# 06_-_Voltage_Sense.net
KiCad netlist of a schematic drawn in Altium Designer
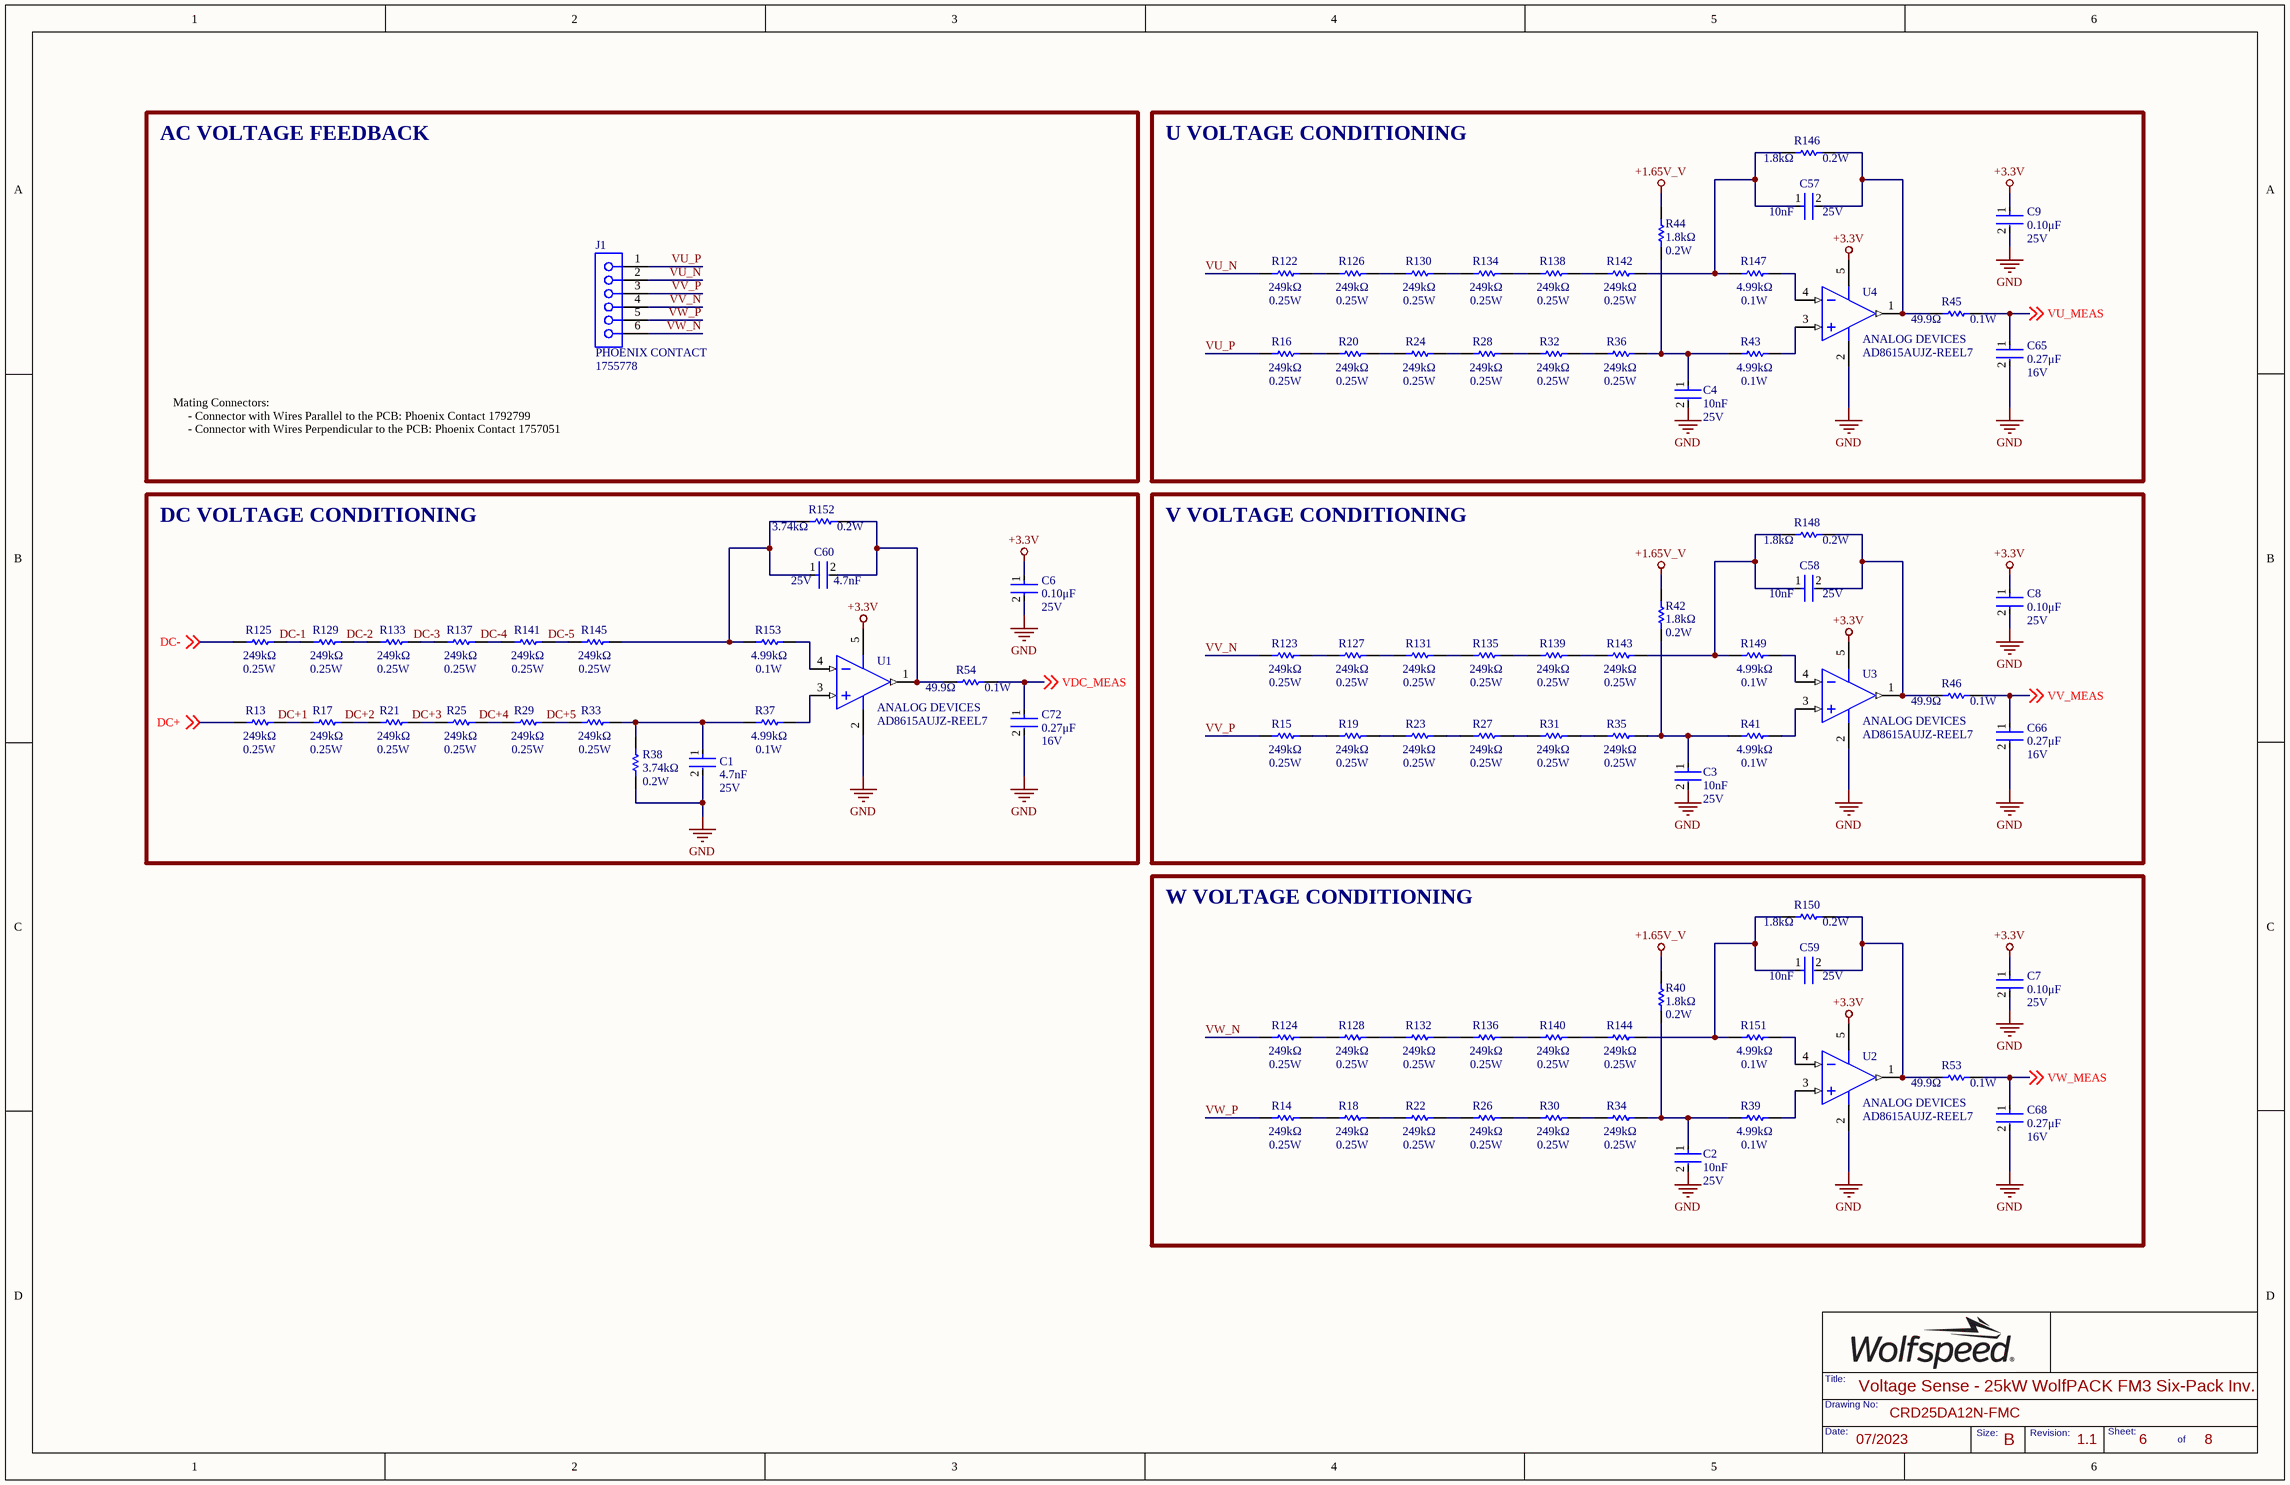
[diagram p0: 06 - Voltage Sense.SchDoc]

(export (version "E")
  (design (tool "Eeschema 10.0.6"))
  (components
    (comp (ref "C1")
      (value "C0603C472K3RAC7867")
      (footprint "FP-C0603C-CF-IPC_B")
      (description "CAP CER 4700PF 25V 10% X7R 0603")
      (fields
        (field (name "MANUFACTURER") "KEMET")
        (field (name "MANUFACTURER PART NUMBER") "C0603C472K3RACTU")
        (field (name "VOLTAGE RATING") "25V")
        (field (name "CAPACITANCE") "4.7nF")
      )
      (libsource (lib "Inverter_25kW") (part "C0603C472K3RAC7867"))
    )
    (comp (ref "C2")
      (value "10nF")
      (footprint "FP-C0603C-CF-IPC_B")
      (description "CAP CER 10000PF 25V X7R 0603")
      (fields
        (field (name "MANUFACTURER") "SAMSUNG")
        (field (name "MANUFACTURER PART NUMBER") "CL10B103KA8WPNC")
        (field (name "VOLTAGE RATING") "25V")
      )
      (libsource (lib "Inverter_25kW") (part "CL10B103KA8WPNC"))
    )
    (comp (ref "C3")
      (value "10nF")
      (footprint "FP-C0603C-CF-IPC_B")
      (description "CAP CER 10000PF 25V X7R 0603")
      (fields
        (field (name "MANUFACTURER") "SAMSUNG")
        (field (name "MANUFACTURER PART NUMBER") "CL10B103KA8WPNC")
        (field (name "VOLTAGE RATING") "25V")
      )
      (libsource (lib "Inverter_25kW") (part "CL10B103KA8WPNC"))
    )
    (comp (ref "C4")
      (value "10nF")
      (footprint "FP-C0603C-CF-IPC_B")
      (description "CAP CER 10000PF 25V X7R 0603")
      (fields
        (field (name "MANUFACTURER") "SAMSUNG")
        (field (name "MANUFACTURER PART NUMBER") "CL10B103KA8WPNC")
        (field (name "VOLTAGE RATING") "25V")
      )
      (libsource (lib "Inverter_25kW") (part "CL10B103KA8WPNC"))
    )
    (comp (ref "C6")
      (value "C0603C104K3RACTU")
      (footprint "FP-C0603C-CF-IPC_B")
      (description "CAP CER 0.1UF 25V X7R 0603")
      (fields
        (field (name "VOLTAGE RATING") "25V")
        (field (name "OCTOPART") "https://octopart.com/c0603c104k3ractu-kemet-127541")
        (field (name "MANUFACTURER") "KEMET")
        (field (name "CAPACITANCE") "0.10μF")
      )
      (libsource (lib "Altium Content Vault") (part "b4654b650e69147ec39a6b967a45e02"))
    )
    (comp (ref "C7")
      (value "C0603C104K3RACTU")
      (footprint "FP-C0603C-CF-IPC_B")
      (description "CAP CER 0.1UF 25V X7R 0603")
      (fields
        (field (name "VOLTAGE RATING") "25V")
        (field (name "OCTOPART") "https://octopart.com/c0603c104k3ractu-kemet-127541")
        (field (name "MANUFACTURER") "KEMET")
        (field (name "CAPACITANCE") "0.10μF")
      )
      (libsource (lib "Altium Content Vault") (part "b4654b650e69147ec39a6b967a45e02"))
    )
    (comp (ref "C8")
      (value "C0603C104K3RACTU")
      (footprint "FP-C0603C-CF-IPC_B")
      (description "CAP CER 0.1UF 25V X7R 0603")
      (fields
        (field (name "VOLTAGE RATING") "25V")
        (field (name "OCTOPART") "https://octopart.com/c0603c104k3ractu-kemet-127541")
        (field (name "MANUFACTURER") "KEMET")
        (field (name "CAPACITANCE") "0.10μF")
      )
      (libsource (lib "Altium Content Vault") (part "b4654b650e69147ec39a6b967a45e02"))
    )
    (comp (ref "C9")
      (value "C0603C104K3RACTU")
      (footprint "FP-C0603C-CF-IPC_B")
      (description "CAP CER 0.1UF 25V X7R 0603")
      (fields
        (field (name "VOLTAGE RATING") "25V")
        (field (name "OCTOPART") "https://octopart.com/c0603c104k3ractu-kemet-127541")
        (field (name "MANUFACTURER") "KEMET")
        (field (name "CAPACITANCE") "0.10μF")
      )
      (libsource (lib "Altium Content Vault") (part "b4654b650e69147ec39a6b967a45e02"))
    )
    (comp (ref "C57")
      (value "10nF")
      (footprint "FP-C0603C-CF-IPC_B")
      (description "CAP CER 10000PF 25V X7R 0603")
      (fields
        (field (name "MANUFACTURER") "SAMSUNG")
        (field (name "MANUFACTURER PART NUMBER") "CL10B103KA8WPNC")
        (field (name "VOLTAGE RATING") "25V")
      )
      (libsource (lib "Inverter_25kW") (part "CL10B103KA8WPNC"))
    )
    (comp (ref "C58")
      (value "10nF")
      (footprint "FP-C0603C-CF-IPC_B")
      (description "CAP CER 10000PF 25V X7R 0603")
      (fields
        (field (name "MANUFACTURER") "SAMSUNG")
        (field (name "MANUFACTURER PART NUMBER") "CL10B103KA8WPNC")
        (field (name "VOLTAGE RATING") "25V")
      )
      (libsource (lib "Inverter_25kW") (part "CL10B103KA8WPNC"))
    )
    (comp (ref "C59")
      (value "10nF")
      (footprint "FP-C0603C-CF-IPC_B")
      (description "CAP CER 10000PF 25V X7R 0603")
      (fields
        (field (name "MANUFACTURER") "SAMSUNG")
        (field (name "MANUFACTURER PART NUMBER") "CL10B103KA8WPNC")
        (field (name "VOLTAGE RATING") "25V")
      )
      (libsource (lib "Inverter_25kW") (part "CL10B103KA8WPNC"))
    )
    (comp (ref "C60")
      (value "C0603C472K3RAC7867")
      (footprint "FP-C0603C-CF-IPC_B")
      (description "CAP CER 4700PF 25V 10% X7R 0603")
      (fields
        (field (name "MANUFACTURER") "KEMET")
        (field (name "MANUFACTURER PART NUMBER") "C0603C472K3RACTU")
        (field (name "VOLTAGE RATING") "25V")
        (field (name "CAPACITANCE") "4.7nF")
      )
      (libsource (lib "Inverter_25kW") (part "C0603C472K3RAC7867"))
    )
    (comp (ref "C65")
      (value "GCM188R71C274KA37D")
      (footprint "FP-GCM188-0_1-IPC_A")
      (description "CAP CER 0.27UF 16V X7R 0603")
      (fields
        (field (name "VOLTAGE RATING (DC)") "16V")
        (field (name "CAPACITANCE") "0.27μF")
        (field (name "TOLERANCE") "10%")
        (field (name "MANUFACTURER") "MURATA")
      )
      (libsource (lib "Altium Content Vault") (part "02cd4be3c70576c341d710602a673aa"))
    )
    (comp (ref "C66")
      (value "GCM188R71C274KA37D")
      (footprint "FP-GCM188-0_1-IPC_A")
      (description "CAP CER 0.27UF 16V X7R 0603")
      (fields
        (field (name "VOLTAGE RATING (DC)") "16V")
        (field (name "CAPACITANCE") "0.27μF")
        (field (name "TOLERANCE") "10%")
        (field (name "MANUFACTURER") "MURATA")
      )
      (libsource (lib "Altium Content Vault") (part "02cd4be3c70576c341d710602a673aa"))
    )
    (comp (ref "C68")
      (value "GCM188R71C274KA37D")
      (footprint "FP-GCM188-0_1-IPC_A")
      (description "CAP CER 0.27UF 16V X7R 0603")
      (fields
        (field (name "VOLTAGE RATING (DC)") "16V")
        (field (name "CAPACITANCE") "0.27μF")
        (field (name "TOLERANCE") "10%")
        (field (name "MANUFACTURER") "MURATA")
      )
      (libsource (lib "Altium Content Vault") (part "02cd4be3c70576c341d710602a673aa"))
    )
    (comp (ref "C72")
      (value "GCM188R71C274KA37D")
      (footprint "FP-GCM188-0_1-IPC_A")
      (description "CAP CER 0.27UF 16V X7R 0603")
      (fields
        (field (name "VOLTAGE RATING (DC)") "16V")
        (field (name "CAPACITANCE") "0.27μF")
        (field (name "TOLERANCE") "10%")
        (field (name "MANUFACTURER") "MURATA")
      )
      (libsource (lib "Altium Content Vault") (part "02cd4be3c70576c341d710602a673aa"))
    )
    (comp (ref "J1")
      (value "1755778")
      (footprint "Inverter_25kW:1755778")
      (description "TERM BLOCK HDR 6POS VERT 5.08MM")
      (fields
        (field (name "MANUFACTURER") "PHOENIX CONTACT")
        (field (name "VOLTAGE") "300V")
        (field (name "MANUFACTURER PRINT") "PHOENIX CONTACT")
      )
      (libsource (lib "Inverter_25kW") (part "1755778"))
    )
    (comp (ref "R13")
      (value "TNPW1206249KBEEA")
      (footprint "RESC3216X65X50NL15T25")
      (description "RES 249K OHM 0.1% 1/4W 1206")
      (fields
        (field (name "MANUFACTURER") "VISHAY DALE")
        (field (name "RESISTANCE") "249kΩ")
        (field (name "POWER") "0.25W")
      )
      (libsource (lib "Altium Content Vault") (part "RES"))
    )
    (comp (ref "R14")
      (value "TNPW1206249KBEEA")
      (footprint "RESC3216X65X50NL15T25")
      (description "RES 249K OHM 0.1% 1/4W 1206")
      (fields
        (field (name "MANUFACTURER") "VISHAY DALE")
        (field (name "RESISTANCE") "249kΩ")
        (field (name "POWER") "0.25W")
      )
      (libsource (lib "Altium Content Vault") (part "RES"))
    )
    (comp (ref "R15")
      (value "TNPW1206249KBEEA")
      (footprint "RESC3216X65X50NL15T25")
      (description "RES 249K OHM 0.1% 1/4W 1206")
      (fields
        (field (name "MANUFACTURER") "VISHAY DALE")
        (field (name "RESISTANCE") "249kΩ")
        (field (name "POWER") "0.25W")
      )
      (libsource (lib "Altium Content Vault") (part "RES"))
    )
    (comp (ref "R16")
      (value "TNPW1206249KBEEA")
      (footprint "RESC3216X65X50NL15T25")
      (description "RES 249K OHM 0.1% 1/4W 1206")
      (fields
        (field (name "MANUFACTURER") "VISHAY DALE")
        (field (name "RESISTANCE") "249kΩ")
        (field (name "POWER") "0.25W")
      )
      (libsource (lib "Altium Content Vault") (part "RES"))
    )
    (comp (ref "R17")
      (value "TNPW1206249KBEEA")
      (footprint "RESC3216X65X50NL15T25")
      (description "RES 249K OHM 0.1% 1/4W 1206")
      (fields
        (field (name "MANUFACTURER") "VISHAY DALE")
        (field (name "RESISTANCE") "249kΩ")
        (field (name "POWER") "0.25W")
      )
      (libsource (lib "Altium Content Vault") (part "RES"))
    )
    (comp (ref "R18")
      (value "TNPW1206249KBEEA")
      (footprint "RESC3216X65X50NL15T25")
      (description "RES 249K OHM 0.1% 1/4W 1206")
      (fields
        (field (name "MANUFACTURER") "VISHAY DALE")
        (field (name "RESISTANCE") "249kΩ")
        (field (name "POWER") "0.25W")
      )
      (libsource (lib "Altium Content Vault") (part "RES"))
    )
    (comp (ref "R19")
      (value "TNPW1206249KBEEA")
      (footprint "RESC3216X65X50NL15T25")
      (description "RES 249K OHM 0.1% 1/4W 1206")
      (fields
        (field (name "MANUFACTURER") "VISHAY DALE")
        (field (name "RESISTANCE") "249kΩ")
        (field (name "POWER") "0.25W")
      )
      (libsource (lib "Altium Content Vault") (part "RES"))
    )
    (comp (ref "R20")
      (value "TNPW1206249KBEEA")
      (footprint "RESC3216X65X50NL15T25")
      (description "RES 249K OHM 0.1% 1/4W 1206")
      (fields
        (field (name "MANUFACTURER") "VISHAY DALE")
        (field (name "RESISTANCE") "249kΩ")
        (field (name "POWER") "0.25W")
      )
      (libsource (lib "Altium Content Vault") (part "RES"))
    )
    (comp (ref "R21")
      (value "TNPW1206249KBEEA")
      (footprint "RESC3216X65X50NL15T25")
      (description "RES 249K OHM 0.1% 1/4W 1206")
      (fields
        (field (name "MANUFACTURER") "VISHAY DALE")
        (field (name "RESISTANCE") "249kΩ")
        (field (name "POWER") "0.25W")
      )
      (libsource (lib "Altium Content Vault") (part "RES"))
    )
    (comp (ref "R22")
      (value "TNPW1206249KBEEA")
      (footprint "RESC3216X65X50NL15T25")
      (description "RES 249K OHM 0.1% 1/4W 1206")
      (fields
        (field (name "MANUFACTURER") "VISHAY DALE")
        (field (name "RESISTANCE") "249kΩ")
        (field (name "POWER") "0.25W")
      )
      (libsource (lib "Altium Content Vault") (part "RES"))
    )
    (comp (ref "R23")
      (value "TNPW1206249KBEEA")
      (footprint "RESC3216X65X50NL15T25")
      (description "RES 249K OHM 0.1% 1/4W 1206")
      (fields
        (field (name "MANUFACTURER") "VISHAY DALE")
        (field (name "RESISTANCE") "249kΩ")
        (field (name "POWER") "0.25W")
      )
      (libsource (lib "Altium Content Vault") (part "RES"))
    )
    (comp (ref "R24")
      (value "TNPW1206249KBEEA")
      (footprint "RESC3216X65X50NL15T25")
      (description "RES 249K OHM 0.1% 1/4W 1206")
      (fields
        (field (name "MANUFACTURER") "VISHAY DALE")
        (field (name "RESISTANCE") "249kΩ")
        (field (name "POWER") "0.25W")
      )
      (libsource (lib "Altium Content Vault") (part "RES"))
    )
    (comp (ref "R25")
      (value "TNPW1206249KBEEA")
      (footprint "RESC3216X65X50NL15T25")
      (description "RES 249K OHM 0.1% 1/4W 1206")
      (fields
        (field (name "MANUFACTURER") "VISHAY DALE")
        (field (name "RESISTANCE") "249kΩ")
        (field (name "POWER") "0.25W")
      )
      (libsource (lib "Altium Content Vault") (part "RES"))
    )
    (comp (ref "R26")
      (value "TNPW1206249KBEEA")
      (footprint "RESC3216X65X50NL15T25")
      (description "RES 249K OHM 0.1% 1/4W 1206")
      (fields
        (field (name "MANUFACTURER") "VISHAY DALE")
        (field (name "RESISTANCE") "249kΩ")
        (field (name "POWER") "0.25W")
      )
      (libsource (lib "Altium Content Vault") (part "RES"))
    )
    (comp (ref "R27")
      (value "TNPW1206249KBEEA")
      (footprint "RESC3216X65X50NL15T25")
      (description "RES 249K OHM 0.1% 1/4W 1206")
      (fields
        (field (name "MANUFACTURER") "VISHAY DALE")
        (field (name "RESISTANCE") "249kΩ")
        (field (name "POWER") "0.25W")
      )
      (libsource (lib "Altium Content Vault") (part "RES"))
    )
    (comp (ref "R28")
      (value "TNPW1206249KBEEA")
      (footprint "RESC3216X65X50NL15T25")
      (description "RES 249K OHM 0.1% 1/4W 1206")
      (fields
        (field (name "MANUFACTURER") "VISHAY DALE")
        (field (name "RESISTANCE") "249kΩ")
        (field (name "POWER") "0.25W")
      )
      (libsource (lib "Altium Content Vault") (part "RES"))
    )
    (comp (ref "R29")
      (value "TNPW1206249KBEEA")
      (footprint "RESC3216X65X50NL15T25")
      (description "RES 249K OHM 0.1% 1/4W 1206")
      (fields
        (field (name "MANUFACTURER") "VISHAY DALE")
        (field (name "RESISTANCE") "249kΩ")
        (field (name "POWER") "0.25W")
      )
      (libsource (lib "Altium Content Vault") (part "RES"))
    )
    (comp (ref "R30")
      (value "TNPW1206249KBEEA")
      (footprint "RESC3216X65X50NL15T25")
      (description "RES 249K OHM 0.1% 1/4W 1206")
      (fields
        (field (name "MANUFACTURER") "VISHAY DALE")
        (field (name "RESISTANCE") "249kΩ")
        (field (name "POWER") "0.25W")
      )
      (libsource (lib "Altium Content Vault") (part "RES"))
    )
    (comp (ref "R31")
      (value "TNPW1206249KBEEA")
      (footprint "RESC3216X65X50NL15T25")
      (description "RES 249K OHM 0.1% 1/4W 1206")
      (fields
        (field (name "MANUFACTURER") "VISHAY DALE")
        (field (name "RESISTANCE") "249kΩ")
        (field (name "POWER") "0.25W")
      )
      (libsource (lib "Altium Content Vault") (part "RES"))
    )
    (comp (ref "R32")
      (value "TNPW1206249KBEEA")
      (footprint "RESC3216X65X50NL15T25")
      (description "RES 249K OHM 0.1% 1/4W 1206")
      (fields
        (field (name "MANUFACTURER") "VISHAY DALE")
        (field (name "RESISTANCE") "249kΩ")
        (field (name "POWER") "0.25W")
      )
      (libsource (lib "Altium Content Vault") (part "RES"))
    )
    (comp (ref "R33")
      (value "TNPW1206249KBEEA")
      (footprint "RESC3216X65X50NL15T25")
      (description "RES 249K OHM 0.1% 1/4W 1206")
      (fields
        (field (name "MANUFACTURER") "VISHAY DALE")
        (field (name "RESISTANCE") "249kΩ")
        (field (name "POWER") "0.25W")
      )
      (libsource (lib "Altium Content Vault") (part "RES"))
    )
    (comp (ref "R34")
      (value "TNPW1206249KBEEA")
      (footprint "RESC3216X65X50NL15T25")
      (description "RES 249K OHM 0.1% 1/4W 1206")
      (fields
        (field (name "MANUFACTURER") "VISHAY DALE")
        (field (name "RESISTANCE") "249kΩ")
        (field (name "POWER") "0.25W")
      )
      (libsource (lib "Altium Content Vault") (part "RES"))
    )
    (comp (ref "R35")
      (value "TNPW1206249KBEEA")
      (footprint "RESC3216X65X50NL15T25")
      (description "RES 249K OHM 0.1% 1/4W 1206")
      (fields
        (field (name "MANUFACTURER") "VISHAY DALE")
        (field (name "RESISTANCE") "249kΩ")
        (field (name "POWER") "0.25W")
      )
      (libsource (lib "Altium Content Vault") (part "RES"))
    )
    (comp (ref "R36")
      (value "TNPW1206249KBEEA")
      (footprint "RESC3216X65X50NL15T25")
      (description "RES 249K OHM 0.1% 1/4W 1206")
      (fields
        (field (name "MANUFACTURER") "VISHAY DALE")
        (field (name "RESISTANCE") "249kΩ")
        (field (name "POWER") "0.25W")
      )
      (libsource (lib "Altium Content Vault") (part "RES"))
    )
    (comp (ref "R37")
      (value "RC0603FR-074K99L")
      (footprint "FP-MCR03-IPC_B")
      (description "RES 4.99K OHM 1% 1/10W 0603")
      (fields
        (field (name "MANUFACTURER") "YAGEO")
        (field (name "TOLERANCE") "1%")
        (field (name "POWER RATING") "0.1W")
        (field (name "RESISTANCE") "4.99kΩ")
      )
      (libsource (lib "Inverter_25kW") (part "RC0603FR-074K99L"))
    )
    (comp (ref "R38")
      (value "ERJ-PB3B3741V")
      (footprint "FP-MCR03-IPC_B")
      (description "RES SMD 3.74K OHM 0.1% 1/5W 0603")
      (fields
        (field (name "MANUFACTURER") "PANASONIC")
        (field (name "TOLERANCE") "0.1%")
        (field (name "MAX POWER DISSIPATION") "0.2W")
        (field (name "RESISTANCE") "3.74kΩ")
      )
      (libsource (lib "Inverter_25kW") (part "ERJ-PB3B3741V"))
    )
    (comp (ref "R39")
      (value "RC0603FR-074K99L")
      (footprint "FP-MCR03-IPC_B")
      (description "RES 4.99K OHM 1% 1/10W 0603")
      (fields
        (field (name "MANUFACTURER") "YAGEO")
        (field (name "TOLERANCE") "1%")
        (field (name "POWER RATING") "0.1W")
        (field (name "RESISTANCE") "4.99kΩ")
      )
      (libsource (lib "Inverter_25kW") (part "RC0603FR-074K99L"))
    )
    (comp (ref "R40")
      (value "ERJ-PB3B1801V")
      (footprint "FP-MCR03-IPC_B")
      (description "RES SMD 1.8K OHM 0.1% 1/5W 0603")
      (fields
        (field (name "MANUFACTURER") "PANASONIC")
        (field (name "TOLERANCE") "0.1%")
        (field (name "RESISTANCE") "1.8kΩ")
        (field (name "MAX POWER DISSIPATION") "0.2W")
      )
      (libsource (lib "Inverter_25kW") (part "ERJ-PB3B1801V"))
    )
    (comp (ref "R41")
      (value "RC0603FR-074K99L")
      (footprint "FP-MCR03-IPC_B")
      (description "RES 4.99K OHM 1% 1/10W 0603")
      (fields
        (field (name "MANUFACTURER") "YAGEO")
        (field (name "TOLERANCE") "1%")
        (field (name "POWER RATING") "0.1W")
        (field (name "RESISTANCE") "4.99kΩ")
      )
      (libsource (lib "Inverter_25kW") (part "RC0603FR-074K99L"))
    )
    (comp (ref "R42")
      (value "ERJ-PB3B1801V")
      (footprint "FP-MCR03-IPC_B")
      (description "RES SMD 1.8K OHM 0.1% 1/5W 0603")
      (fields
        (field (name "MANUFACTURER") "PANASONIC")
        (field (name "TOLERANCE") "0.1%")
        (field (name "RESISTANCE") "1.8kΩ")
        (field (name "MAX POWER DISSIPATION") "0.2W")
      )
      (libsource (lib "Inverter_25kW") (part "ERJ-PB3B1801V"))
    )
    (comp (ref "R43")
      (value "RC0603FR-074K99L")
      (footprint "FP-MCR03-IPC_B")
      (description "RES 4.99K OHM 1% 1/10W 0603")
      (fields
        (field (name "MANUFACTURER") "YAGEO")
        (field (name "TOLERANCE") "1%")
        (field (name "POWER RATING") "0.1W")
        (field (name "RESISTANCE") "4.99kΩ")
      )
      (libsource (lib "Inverter_25kW") (part "RC0603FR-074K99L"))
    )
    (comp (ref "R44")
      (value "ERJ-PB3B1801V")
      (footprint "FP-MCR03-IPC_B")
      (description "RES SMD 1.8K OHM 0.1% 1/5W 0603")
      (fields
        (field (name "MANUFACTURER") "PANASONIC")
        (field (name "TOLERANCE") "0.1%")
        (field (name "RESISTANCE") "1.8kΩ")
        (field (name "MAX POWER DISSIPATION") "0.2W")
      )
      (libsource (lib "Inverter_25kW") (part "ERJ-PB3B1801V"))
    )
    (comp (ref "R45")
      (value "ERJ-3EKF49R9V")
      (footprint "FP-MCR03-IPC_B")
      (description "RES SMD 49.9 OHM 1% 1/10W 0603")
      (fields
        (field (name "MANUFACTURER") "PANASONIC")
        (field (name "TOLERANCE") "1%")
        (field (name "RESISTANCE") "49.9Ω")
        (field (name "POWER RATING") "0.1W")
      )
      (libsource (lib "Inverter_25kW") (part "ERJ-3EKF49R9V"))
    )
    (comp (ref "R46")
      (value "ERJ-3EKF49R9V")
      (footprint "FP-MCR03-IPC_B")
      (description "RES SMD 49.9 OHM 1% 1/10W 0603")
      (fields
        (field (name "MANUFACTURER") "PANASONIC")
        (field (name "TOLERANCE") "1%")
        (field (name "RESISTANCE") "49.9Ω")
        (field (name "POWER RATING") "0.1W")
      )
      (libsource (lib "Inverter_25kW") (part "ERJ-3EKF49R9V"))
    )
    (comp (ref "R53")
      (value "ERJ-3EKF49R9V")
      (footprint "FP-MCR03-IPC_B")
      (description "RES SMD 49.9 OHM 1% 1/10W 0603")
      (fields
        (field (name "MANUFACTURER") "PANASONIC")
        (field (name "TOLERANCE") "1%")
        (field (name "RESISTANCE") "49.9Ω")
        (field (name "POWER RATING") "0.1W")
      )
      (libsource (lib "Inverter_25kW") (part "ERJ-3EKF49R9V"))
    )
    (comp (ref "R54")
      (value "ERJ-3EKF49R9V")
      (footprint "FP-MCR03-IPC_B")
      (description "RES SMD 49.9 OHM 1% 1/10W 0603")
      (fields
        (field (name "MANUFACTURER") "PANASONIC")
        (field (name "TOLERANCE") "1%")
        (field (name "RESISTANCE") "49.9Ω")
        (field (name "POWER RATING") "0.1W")
      )
      (libsource (lib "Inverter_25kW") (part "ERJ-3EKF49R9V"))
    )
    (comp (ref "R122")
      (value "TNPW1206249KBEEA")
      (footprint "RESC3216X65X50NL15T25")
      (description "RES 249K OHM 0.1% 1/4W 1206")
      (fields
        (field (name "MANUFACTURER") "VISHAY DALE")
        (field (name "RESISTANCE") "249kΩ")
        (field (name "POWER") "0.25W")
      )
      (libsource (lib "Altium Content Vault") (part "RES"))
    )
    (comp (ref "R123")
      (value "TNPW1206249KBEEA")
      (footprint "RESC3216X65X50NL15T25")
      (description "RES 249K OHM 0.1% 1/4W 1206")
      (fields
        (field (name "MANUFACTURER") "VISHAY DALE")
        (field (name "RESISTANCE") "249kΩ")
        (field (name "POWER") "0.25W")
      )
      (libsource (lib "Altium Content Vault") (part "RES"))
    )
    (comp (ref "R124")
      (value "TNPW1206249KBEEA")
      (footprint "RESC3216X65X50NL15T25")
      (description "RES 249K OHM 0.1% 1/4W 1206")
      (fields
        (field (name "MANUFACTURER") "VISHAY DALE")
        (field (name "RESISTANCE") "249kΩ")
        (field (name "POWER") "0.25W")
      )
      (libsource (lib "Altium Content Vault") (part "RES"))
    )
    (comp (ref "R125")
      (value "TNPW1206249KBEEA")
      (footprint "RESC3216X65X50NL15T25")
      (description "RES 249K OHM 0.1% 1/4W 1206")
      (fields
        (field (name "MANUFACTURER") "VISHAY DALE")
        (field (name "RESISTANCE") "249kΩ")
        (field (name "POWER") "0.25W")
      )
      (libsource (lib "Altium Content Vault") (part "RES"))
    )
    (comp (ref "R126")
      (value "TNPW1206249KBEEA")
      (footprint "RESC3216X65X50NL15T25")
      (description "RES 249K OHM 0.1% 1/4W 1206")
      (fields
        (field (name "MANUFACTURER") "VISHAY DALE")
        (field (name "RESISTANCE") "249kΩ")
        (field (name "POWER") "0.25W")
      )
      (libsource (lib "Altium Content Vault") (part "RES"))
    )
    (comp (ref "R127")
      (value "TNPW1206249KBEEA")
      (footprint "RESC3216X65X50NL15T25")
      (description "RES 249K OHM 0.1% 1/4W 1206")
      (fields
        (field (name "MANUFACTURER") "VISHAY DALE")
        (field (name "RESISTANCE") "249kΩ")
        (field (name "POWER") "0.25W")
      )
      (libsource (lib "Altium Content Vault") (part "RES"))
    )
    (comp (ref "R128")
      (value "TNPW1206249KBEEA")
      (footprint "RESC3216X65X50NL15T25")
      (description "RES 249K OHM 0.1% 1/4W 1206")
      (fields
        (field (name "MANUFACTURER") "VISHAY DALE")
        (field (name "RESISTANCE") "249kΩ")
        (field (name "POWER") "0.25W")
      )
      (libsource (lib "Altium Content Vault") (part "RES"))
    )
    (comp (ref "R129")
      (value "TNPW1206249KBEEA")
      (footprint "RESC3216X65X50NL15T25")
      (description "RES 249K OHM 0.1% 1/4W 1206")
      (fields
        (field (name "MANUFACTURER") "VISHAY DALE")
        (field (name "RESISTANCE") "249kΩ")
        (field (name "POWER") "0.25W")
      )
      (libsource (lib "Altium Content Vault") (part "RES"))
    )
    (comp (ref "R130")
      (value "TNPW1206249KBEEA")
      (footprint "RESC3216X65X50NL15T25")
      (description "RES 249K OHM 0.1% 1/4W 1206")
      (fields
        (field (name "MANUFACTURER") "VISHAY DALE")
        (field (name "RESISTANCE") "249kΩ")
        (field (name "POWER") "0.25W")
      )
      (libsource (lib "Altium Content Vault") (part "RES"))
    )
    (comp (ref "R131")
      (value "TNPW1206249KBEEA")
      (footprint "RESC3216X65X50NL15T25")
      (description "RES 249K OHM 0.1% 1/4W 1206")
      (fields
        (field (name "MANUFACTURER") "VISHAY DALE")
        (field (name "RESISTANCE") "249kΩ")
        (field (name "POWER") "0.25W")
      )
      (libsource (lib "Altium Content Vault") (part "RES"))
    )
    (comp (ref "R132")
      (value "TNPW1206249KBEEA")
      (footprint "RESC3216X65X50NL15T25")
      (description "RES 249K OHM 0.1% 1/4W 1206")
      (fields
        (field (name "MANUFACTURER") "VISHAY DALE")
        (field (name "RESISTANCE") "249kΩ")
        (field (name "POWER") "0.25W")
      )
      (libsource (lib "Altium Content Vault") (part "RES"))
    )
    (comp (ref "R133")
      (value "TNPW1206249KBEEA")
      (footprint "RESC3216X65X50NL15T25")
      (description "RES 249K OHM 0.1% 1/4W 1206")
      (fields
        (field (name "MANUFACTURER") "VISHAY DALE")
        (field (name "RESISTANCE") "249kΩ")
        (field (name "POWER") "0.25W")
      )
      (libsource (lib "Altium Content Vault") (part "RES"))
    )
    (comp (ref "R134")
      (value "TNPW1206249KBEEA")
      (footprint "RESC3216X65X50NL15T25")
      (description "RES 249K OHM 0.1% 1/4W 1206")
      (fields
        (field (name "MANUFACTURER") "VISHAY DALE")
        (field (name "RESISTANCE") "249kΩ")
        (field (name "POWER") "0.25W")
      )
      (libsource (lib "Altium Content Vault") (part "RES"))
    )
    (comp (ref "R135")
      (value "TNPW1206249KBEEA")
      (footprint "RESC3216X65X50NL15T25")
      (description "RES 249K OHM 0.1% 1/4W 1206")
      (fields
        (field (name "MANUFACTURER") "VISHAY DALE")
        (field (name "RESISTANCE") "249kΩ")
        (field (name "POWER") "0.25W")
      )
      (libsource (lib "Altium Content Vault") (part "RES"))
    )
    (comp (ref "R136")
      (value "TNPW1206249KBEEA")
      (footprint "RESC3216X65X50NL15T25")
      (description "RES 249K OHM 0.1% 1/4W 1206")
      (fields
        (field (name "MANUFACTURER") "VISHAY DALE")
        (field (name "RESISTANCE") "249kΩ")
        (field (name "POWER") "0.25W")
      )
      (libsource (lib "Altium Content Vault") (part "RES"))
    )
    (comp (ref "R137")
      (value "TNPW1206249KBEEA")
      (footprint "RESC3216X65X50NL15T25")
      (description "RES 249K OHM 0.1% 1/4W 1206")
      (fields
        (field (name "MANUFACTURER") "VISHAY DALE")
        (field (name "RESISTANCE") "249kΩ")
        (field (name "POWER") "0.25W")
      )
      (libsource (lib "Altium Content Vault") (part "RES"))
    )
    (comp (ref "R138")
      (value "TNPW1206249KBEEA")
      (footprint "RESC3216X65X50NL15T25")
      (description "RES 249K OHM 0.1% 1/4W 1206")
      (fields
        (field (name "MANUFACTURER") "VISHAY DALE")
        (field (name "RESISTANCE") "249kΩ")
        (field (name "POWER") "0.25W")
      )
      (libsource (lib "Altium Content Vault") (part "RES"))
    )
    (comp (ref "R139")
      (value "TNPW1206249KBEEA")
      (footprint "RESC3216X65X50NL15T25")
      (description "RES 249K OHM 0.1% 1/4W 1206")
      (fields
        (field (name "MANUFACTURER") "VISHAY DALE")
        (field (name "RESISTANCE") "249kΩ")
        (field (name "POWER") "0.25W")
      )
      (libsource (lib "Altium Content Vault") (part "RES"))
    )
    (comp (ref "R140")
      (value "TNPW1206249KBEEA")
      (footprint "RESC3216X65X50NL15T25")
      (description "RES 249K OHM 0.1% 1/4W 1206")
      (fields
        (field (name "MANUFACTURER") "VISHAY DALE")
        (field (name "RESISTANCE") "249kΩ")
        (field (name "POWER") "0.25W")
      )
      (libsource (lib "Altium Content Vault") (part "RES"))
    )
    (comp (ref "R141")
      (value "TNPW1206249KBEEA")
      (footprint "RESC3216X65X50NL15T25")
      (description "RES 249K OHM 0.1% 1/4W 1206")
      (fields
        (field (name "MANUFACTURER") "VISHAY DALE")
        (field (name "RESISTANCE") "249kΩ")
        (field (name "POWER") "0.25W")
      )
      (libsource (lib "Altium Content Vault") (part "RES"))
    )
    (comp (ref "R142")
      (value "TNPW1206249KBEEA")
      (footprint "RESC3216X65X50NL15T25")
      (description "RES 249K OHM 0.1% 1/4W 1206")
      (fields
        (field (name "MANUFACTURER") "VISHAY DALE")
        (field (name "RESISTANCE") "249kΩ")
        (field (name "POWER") "0.25W")
      )
      (libsource (lib "Altium Content Vault") (part "RES"))
    )
    (comp (ref "R143")
      (value "TNPW1206249KBEEA")
      (footprint "RESC3216X65X50NL15T25")
      (description "RES 249K OHM 0.1% 1/4W 1206")
      (fields
        (field (name "MANUFACTURER") "VISHAY DALE")
        (field (name "RESISTANCE") "249kΩ")
        (field (name "POWER") "0.25W")
      )
      (libsource (lib "Altium Content Vault") (part "RES"))
    )
    (comp (ref "R144")
      (value "TNPW1206249KBEEA")
      (footprint "RESC3216X65X50NL15T25")
      (description "RES 249K OHM 0.1% 1/4W 1206")
      (fields
        (field (name "MANUFACTURER") "VISHAY DALE")
        (field (name "RESISTANCE") "249kΩ")
        (field (name "POWER") "0.25W")
      )
      (libsource (lib "Altium Content Vault") (part "RES"))
    )
    (comp (ref "R145")
      (value "TNPW1206249KBEEA")
      (footprint "RESC3216X65X50NL15T25")
      (description "RES 249K OHM 0.1% 1/4W 1206")
      (fields
        (field (name "MANUFACTURER") "VISHAY DALE")
        (field (name "RESISTANCE") "249kΩ")
        (field (name "POWER") "0.25W")
      )
      (libsource (lib "Altium Content Vault") (part "RES"))
    )
    (comp (ref "R146")
      (value "ERJ-PB3B1801V")
      (footprint "FP-MCR03-IPC_B")
      (description "RES SMD 1.8K OHM 0.1% 1/5W 0603")
      (fields
        (field (name "MANUFACTURER") "PANASONIC")
        (field (name "TOLERANCE") "0.1%")
        (field (name "RESISTANCE") "1.8kΩ")
        (field (name "MAX POWER DISSIPATION") "0.2W")
      )
      (libsource (lib "Inverter_25kW") (part "ERJ-PB3B1801V"))
    )
    (comp (ref "R147")
      (value "RC0603FR-074K99L")
      (footprint "FP-MCR03-IPC_B")
      (description "RES 4.99K OHM 1% 1/10W 0603")
      (fields
        (field (name "MANUFACTURER") "YAGEO")
        (field (name "TOLERANCE") "1%")
        (field (name "POWER RATING") "0.1W")
        (field (name "RESISTANCE") "4.99kΩ")
      )
      (libsource (lib "Inverter_25kW") (part "RC0603FR-074K99L"))
    )
    (comp (ref "R148")
      (value "ERJ-PB3B1801V")
      (footprint "FP-MCR03-IPC_B")
      (description "RES SMD 1.8K OHM 0.1% 1/5W 0603")
      (fields
        (field (name "MANUFACTURER") "PANASONIC")
        (field (name "TOLERANCE") "0.1%")
        (field (name "RESISTANCE") "1.8kΩ")
        (field (name "MAX POWER DISSIPATION") "0.2W")
      )
      (libsource (lib "Inverter_25kW") (part "ERJ-PB3B1801V"))
    )
    (comp (ref "R149")
      (value "RC0603FR-074K99L")
      (footprint "FP-MCR03-IPC_B")
      (description "RES 4.99K OHM 1% 1/10W 0603")
      (fields
        (field (name "MANUFACTURER") "YAGEO")
        (field (name "TOLERANCE") "1%")
        (field (name "POWER RATING") "0.1W")
        (field (name "RESISTANCE") "4.99kΩ")
      )
      (libsource (lib "Inverter_25kW") (part "RC0603FR-074K99L"))
    )
    (comp (ref "R150")
      (value "ERJ-PB3B1801V")
      (footprint "FP-MCR03-IPC_B")
      (description "RES SMD 1.8K OHM 0.1% 1/5W 0603")
      (fields
        (field (name "MANUFACTURER") "PANASONIC")
        (field (name "TOLERANCE") "0.1%")
        (field (name "RESISTANCE") "1.8kΩ")
        (field (name "MAX POWER DISSIPATION") "0.2W")
      )
      (libsource (lib "Inverter_25kW") (part "ERJ-PB3B1801V"))
    )
    (comp (ref "R151")
      (value "RC0603FR-074K99L")
      (footprint "FP-MCR03-IPC_B")
      (description "RES 4.99K OHM 1% 1/10W 0603")
      (fields
        (field (name "MANUFACTURER") "YAGEO")
        (field (name "TOLERANCE") "1%")
        (field (name "POWER RATING") "0.1W")
        (field (name "RESISTANCE") "4.99kΩ")
      )
      (libsource (lib "Inverter_25kW") (part "RC0603FR-074K99L"))
    )
    (comp (ref "R152")
      (value "ERJ-PB3B3741V")
      (footprint "FP-MCR03-IPC_B")
      (description "RES SMD 3.74K OHM 0.1% 1/5W 0603")
      (fields
        (field (name "MANUFACTURER") "PANASONIC")
        (field (name "TOLERANCE") "0.1%")
        (field (name "MAX POWER DISSIPATION") "0.2W")
        (field (name "RESISTANCE") "3.74kΩ")
      )
      (libsource (lib "Inverter_25kW") (part "ERJ-PB3B3741V"))
    )
    (comp (ref "R153")
      (value "RC0603FR-074K99L")
      (footprint "FP-MCR03-IPC_B")
      (description "RES 4.99K OHM 1% 1/10W 0603")
      (fields
        (field (name "MANUFACTURER") "YAGEO")
        (field (name "TOLERANCE") "1%")
        (field (name "POWER RATING") "0.1W")
        (field (name "RESISTANCE") "4.99kΩ")
      )
      (libsource (lib "Inverter_25kW") (part "RC0603FR-074K99L"))
    )
    (comp (ref "U1")
      (value "AD8615AUJZ-REEL7")
      (footprint "ADI-UJ-5_M")
      (description "IC OPAMP GP 1 CIRCUIT TSOT23-5")
      (fields
        (field (name "MANUFACTURER") "ANALOG DEVICES")
        (field (name "GENERIC PART NUMBER") "AD8615")
        (field (name "MANUFACTURER PART NUMBER") "AD8615AUJZ-REEL7")
      )
      (libsource (lib "Altium Content Vault") (part "ADI-ADxxxx-X-5"))
    )
    (comp (ref "U2")
      (value "AD8615AUJZ-REEL7")
      (footprint "ADI-UJ-5_M")
      (description "IC OPAMP GP 1 CIRCUIT TSOT23-5")
      (fields
        (field (name "MANUFACTURER") "ANALOG DEVICES")
        (field (name "GENERIC PART NUMBER") "AD8615")
        (field (name "MANUFACTURER PART NUMBER") "AD8615AUJZ-REEL7")
      )
      (libsource (lib "Altium Content Vault") (part "ADI-ADxxxx-X-5"))
    )
    (comp (ref "U3")
      (value "AD8615AUJZ-REEL7")
      (footprint "ADI-UJ-5_M")
      (description "IC OPAMP GP 1 CIRCUIT TSOT23-5")
      (fields
        (field (name "MANUFACTURER") "ANALOG DEVICES")
        (field (name "GENERIC PART NUMBER") "AD8615")
        (field (name "MANUFACTURER PART NUMBER") "AD8615AUJZ-REEL7")
      )
      (libsource (lib "Altium Content Vault") (part "ADI-ADxxxx-X-5"))
    )
    (comp (ref "U4")
      (value "AD8615AUJZ-REEL7")
      (footprint "ADI-UJ-5_M")
      (description "IC OPAMP GP 1 CIRCUIT TSOT23-5")
      (fields
        (field (name "MANUFACTURER") "ANALOG DEVICES")
        (field (name "GENERIC PART NUMBER") "AD8615")
        (field (name "MANUFACTURER PART NUMBER") "AD8615AUJZ-REEL7")
      )
      (libsource (lib "Altium Content Vault") (part "ADI-ADxxxx-X-5"))
    )
  )
  (nets
    (net (code "1") (name "+1.65V_V") (class "Default")
      (node (ref "R40") (pin "2") (pinfunction "2_2") (pintype "passive"))
      (node (ref "R42") (pin "2") (pinfunction "2_2") (pintype "passive"))
      (node (ref "R44") (pin "2") (pinfunction "2_2") (pintype "passive"))
    )
    (net (code "2") (name "+3.3V") (class "Default")
      (node (ref "C6") (pin "1") (pinfunction "1_1") (pintype "passive"))
      (node (ref "C7") (pin "1") (pinfunction "1_1") (pintype "passive"))
      (node (ref "C8") (pin "1") (pinfunction "1_1") (pintype "passive"))
      (node (ref "C9") (pin "1") (pinfunction "1_1") (pintype "passive"))
      (node (ref "U1") (pin "5") (pinfunction "+V_5") (pintype "power_in"))
      (node (ref "U2") (pin "5") (pinfunction "+V_5") (pintype "power_in"))
      (node (ref "U3") (pin "5") (pinfunction "+V_5") (pintype "power_in"))
      (node (ref "U4") (pin "5") (pinfunction "+V_5") (pintype "power_in"))
    )
    (net (code "3") (name "/DC+1") (class "Default")
      (node (ref "R13") (pin "2") (pinfunction "2_2") (pintype "passive"))
      (node (ref "R17") (pin "1") (pinfunction "1_1") (pintype "passive"))
    )
    (net (code "4") (name "/DC+2") (class "Default")
      (node (ref "R17") (pin "2") (pinfunction "2_2") (pintype "passive"))
      (node (ref "R21") (pin "1") (pinfunction "1_1") (pintype "passive"))
    )
    (net (code "5") (name "/DC+3") (class "Default")
      (node (ref "R21") (pin "2") (pinfunction "2_2") (pintype "passive"))
      (node (ref "R25") (pin "1") (pinfunction "1_1") (pintype "passive"))
    )
    (net (code "6") (name "/DC+4") (class "Default")
      (node (ref "R25") (pin "2") (pinfunction "2_2") (pintype "passive"))
      (node (ref "R29") (pin "1") (pinfunction "1_1") (pintype "passive"))
    )
    (net (code "7") (name "/DC+5") (class "Default")
      (node (ref "R29") (pin "2") (pinfunction "2_2") (pintype "passive"))
      (node (ref "R33") (pin "1") (pinfunction "1_1") (pintype "passive"))
    )
    (net (code "8") (name "/DC-1") (class "Default")
      (node (ref "R125") (pin "2") (pinfunction "2_2") (pintype "passive"))
      (node (ref "R129") (pin "1") (pinfunction "1_1") (pintype "passive"))
    )
    (net (code "9") (name "/DC-2") (class "Default")
      (node (ref "R129") (pin "2") (pinfunction "2_2") (pintype "passive"))
      (node (ref "R133") (pin "1") (pinfunction "1_1") (pintype "passive"))
    )
    (net (code "10") (name "/DC-3") (class "Default")
      (node (ref "R133") (pin "2") (pinfunction "2_2") (pintype "passive"))
      (node (ref "R137") (pin "1") (pinfunction "1_1") (pintype "passive"))
    )
    (net (code "11") (name "/DC-4") (class "Default")
      (node (ref "R137") (pin "2") (pinfunction "2_2") (pintype "passive"))
      (node (ref "R141") (pin "1") (pinfunction "1_1") (pintype "passive"))
    )
    (net (code "12") (name "/DC-5") (class "Default")
      (node (ref "R141") (pin "2") (pinfunction "2_2") (pintype "passive"))
      (node (ref "R145") (pin "1") (pinfunction "1_1") (pintype "passive"))
    )
    (net (code "13") (name "/VU_N") (class "Default")
      (node (ref "J1") (pin "2") (pinfunction "2_2") (pintype "passive"))
      (node (ref "R122") (pin "1") (pinfunction "1_1") (pintype "passive"))
    )
    (net (code "14") (name "/VU_P") (class "Default")
      (node (ref "J1") (pin "1") (pinfunction "1_1") (pintype "passive"))
      (node (ref "R16") (pin "1") (pinfunction "1_1") (pintype "passive"))
    )
    (net (code "15") (name "/VV_N") (class "Default")
      (node (ref "J1") (pin "4") (pinfunction "4_4") (pintype "passive"))
      (node (ref "R123") (pin "1") (pinfunction "1_1") (pintype "passive"))
    )
    (net (code "16") (name "/VV_P") (class "Default")
      (node (ref "J1") (pin "3") (pinfunction "3_3") (pintype "passive"))
      (node (ref "R15") (pin "1") (pinfunction "1_1") (pintype "passive"))
    )
    (net (code "17") (name "/VW_N") (class "Default")
      (node (ref "J1") (pin "6") (pinfunction "6_6") (pintype "passive"))
      (node (ref "R124") (pin "1") (pinfunction "1_1") (pintype "passive"))
    )
    (net (code "18") (name "/VW_P") (class "Default")
      (node (ref "J1") (pin "5") (pinfunction "5_5") (pintype "passive"))
      (node (ref "R14") (pin "1") (pinfunction "1_1") (pintype "passive"))
    )
    (net (code "19") (name "DC+") (class "Default")
      (node (ref "R13") (pin "1") (pinfunction "1_1") (pintype "passive"))
    )
    (net (code "20") (name "DC-") (class "Default")
      (node (ref "R125") (pin "1") (pinfunction "1_1") (pintype "passive"))
    )
    (net (code "21") (name "GND") (class "Default")
      (node (ref "C1") (pin "2") (pinfunction "2_2") (pintype "passive"))
      (node (ref "C2") (pin "2") (pinfunction "2_2") (pintype "passive"))
      (node (ref "C3") (pin "2") (pinfunction "2_2") (pintype "passive"))
      (node (ref "C4") (pin "2") (pinfunction "2_2") (pintype "passive"))
      (node (ref "C6") (pin "2") (pinfunction "2_2") (pintype "passive"))
      (node (ref "C65") (pin "2") (pinfunction "2_2") (pintype "passive"))
      (node (ref "C66") (pin "2") (pinfunction "2_2") (pintype "passive"))
      (node (ref "C68") (pin "2") (pinfunction "2_2") (pintype "passive"))
      (node (ref "C7") (pin "2") (pinfunction "2_2") (pintype "passive"))
      (node (ref "C72") (pin "2") (pinfunction "2_2") (pintype "passive"))
      (node (ref "C8") (pin "2") (pinfunction "2_2") (pintype "passive"))
      (node (ref "C9") (pin "2") (pinfunction "2_2") (pintype "passive"))
      (node (ref "R38") (pin "1") (pinfunction "1_1") (pintype "passive"))
      (node (ref "U1") (pin "2") (pinfunction "-V_2") (pintype "power_in"))
      (node (ref "U2") (pin "2") (pinfunction "-V_2") (pintype "power_in"))
      (node (ref "U3") (pin "2") (pinfunction "-V_2") (pintype "power_in"))
      (node (ref "U4") (pin "2") (pinfunction "-V_2") (pintype "power_in"))
    )
    (net (code "22") (name "Net-(C1-Pad1)") (class "Default")
      (node (ref "C1") (pin "1") (pinfunction "1_1") (pintype "passive"))
      (node (ref "R33") (pin "2") (pinfunction "2_2") (pintype "passive"))
      (node (ref "R37") (pin "1") (pinfunction "1_1") (pintype "passive"))
      (node (ref "R38") (pin "2") (pinfunction "2_2") (pintype "passive"))
    )
    (net (code "23") (name "Net-(C2-Pad1)") (class "Default")
      (node (ref "C2") (pin "1") (pinfunction "1_1") (pintype "passive"))
      (node (ref "R34") (pin "2") (pinfunction "2_2") (pintype "passive"))
      (node (ref "R39") (pin "1") (pinfunction "1_1") (pintype "passive"))
      (node (ref "R40") (pin "1") (pinfunction "1_1") (pintype "passive"))
    )
    (net (code "24") (name "Net-(C3-Pad1)") (class "Default")
      (node (ref "C3") (pin "1") (pinfunction "1_1") (pintype "passive"))
      (node (ref "R35") (pin "2") (pinfunction "2_2") (pintype "passive"))
      (node (ref "R41") (pin "1") (pinfunction "1_1") (pintype "passive"))
      (node (ref "R42") (pin "1") (pinfunction "1_1") (pintype "passive"))
    )
    (net (code "25") (name "Net-(C4-Pad1)") (class "Default")
      (node (ref "C4") (pin "1") (pinfunction "1_1") (pintype "passive"))
      (node (ref "R36") (pin "2") (pinfunction "2_2") (pintype "passive"))
      (node (ref "R43") (pin "1") (pinfunction "1_1") (pintype "passive"))
      (node (ref "R44") (pin "1") (pinfunction "1_1") (pintype "passive"))
    )
    (net (code "26") (name "Net-(C57-Pad1)") (class "Default")
      (node (ref "C57") (pin "1") (pinfunction "1_1") (pintype "passive"))
      (node (ref "R142") (pin "2") (pinfunction "2_2") (pintype "passive"))
      (node (ref "R146") (pin "2") (pinfunction "2_2") (pintype "passive"))
      (node (ref "R147") (pin "1") (pinfunction "1_1") (pintype "passive"))
    )
    (net (code "27") (name "Net-(C58-Pad1)") (class "Default")
      (node (ref "C58") (pin "1") (pinfunction "1_1") (pintype "passive"))
      (node (ref "R143") (pin "2") (pinfunction "2_2") (pintype "passive"))
      (node (ref "R148") (pin "2") (pinfunction "2_2") (pintype "passive"))
      (node (ref "R149") (pin "1") (pinfunction "1_1") (pintype "passive"))
    )
    (net (code "28") (name "Net-(C59-Pad1)") (class "Default")
      (node (ref "C59") (pin "1") (pinfunction "1_1") (pintype "passive"))
      (node (ref "R144") (pin "2") (pinfunction "2_2") (pintype "passive"))
      (node (ref "R150") (pin "2") (pinfunction "2_2") (pintype "passive"))
      (node (ref "R151") (pin "1") (pinfunction "1_1") (pintype "passive"))
    )
    (net (code "29") (name "Net-(C60-Pad1)") (class "Default")
      (node (ref "C60") (pin "1") (pinfunction "1_1") (pintype "passive"))
      (node (ref "R145") (pin "2") (pinfunction "2_2") (pintype "passive"))
      (node (ref "R152") (pin "1") (pinfunction "1_1") (pintype "passive"))
      (node (ref "R153") (pin "1") (pinfunction "1_1") (pintype "passive"))
    )
    (net (code "30") (name "Net-(R14-Pad2)") (class "Default")
      (node (ref "R14") (pin "2") (pinfunction "2_2") (pintype "passive"))
      (node (ref "R18") (pin "1") (pinfunction "1_1") (pintype "passive"))
    )
    (net (code "31") (name "Net-(R15-Pad2)") (class "Default")
      (node (ref "R15") (pin "2") (pinfunction "2_2") (pintype "passive"))
      (node (ref "R19") (pin "1") (pinfunction "1_1") (pintype "passive"))
    )
    (net (code "32") (name "Net-(R16-Pad2)") (class "Default")
      (node (ref "R16") (pin "2") (pinfunction "2_2") (pintype "passive"))
      (node (ref "R20") (pin "1") (pinfunction "1_1") (pintype "passive"))
    )
    (net (code "33") (name "Net-(R18-Pad2)") (class "Default")
      (node (ref "R18") (pin "2") (pinfunction "2_2") (pintype "passive"))
      (node (ref "R22") (pin "1") (pinfunction "1_1") (pintype "passive"))
    )
    (net (code "34") (name "Net-(R19-Pad2)") (class "Default")
      (node (ref "R19") (pin "2") (pinfunction "2_2") (pintype "passive"))
      (node (ref "R23") (pin "1") (pinfunction "1_1") (pintype "passive"))
    )
    (net (code "35") (name "Net-(R20-Pad2)") (class "Default")
      (node (ref "R20") (pin "2") (pinfunction "2_2") (pintype "passive"))
      (node (ref "R24") (pin "1") (pinfunction "1_1") (pintype "passive"))
    )
    (net (code "36") (name "Net-(R22-Pad2)") (class "Default")
      (node (ref "R22") (pin "2") (pinfunction "2_2") (pintype "passive"))
      (node (ref "R26") (pin "1") (pinfunction "1_1") (pintype "passive"))
    )
    (net (code "37") (name "Net-(R23-Pad2)") (class "Default")
      (node (ref "R23") (pin "2") (pinfunction "2_2") (pintype "passive"))
      (node (ref "R27") (pin "1") (pinfunction "1_1") (pintype "passive"))
    )
    (net (code "38") (name "Net-(R24-Pad2)") (class "Default")
      (node (ref "R24") (pin "2") (pinfunction "2_2") (pintype "passive"))
      (node (ref "R28") (pin "1") (pinfunction "1_1") (pintype "passive"))
    )
    (net (code "39") (name "Net-(R26-Pad2)") (class "Default")
      (node (ref "R26") (pin "2") (pinfunction "2_2") (pintype "passive"))
      (node (ref "R30") (pin "1") (pinfunction "1_1") (pintype "passive"))
    )
    (net (code "40") (name "Net-(R27-Pad2)") (class "Default")
      (node (ref "R27") (pin "2") (pinfunction "2_2") (pintype "passive"))
      (node (ref "R31") (pin "1") (pinfunction "1_1") (pintype "passive"))
    )
    (net (code "41") (name "Net-(R28-Pad2)") (class "Default")
      (node (ref "R28") (pin "2") (pinfunction "2_2") (pintype "passive"))
      (node (ref "R32") (pin "1") (pinfunction "1_1") (pintype "passive"))
    )
    (net (code "42") (name "Net-(R30-Pad2)") (class "Default")
      (node (ref "R30") (pin "2") (pinfunction "2_2") (pintype "passive"))
      (node (ref "R34") (pin "1") (pinfunction "1_1") (pintype "passive"))
    )
    (net (code "43") (name "Net-(R31-Pad2)") (class "Default")
      (node (ref "R31") (pin "2") (pinfunction "2_2") (pintype "passive"))
      (node (ref "R35") (pin "1") (pinfunction "1_1") (pintype "passive"))
    )
    (net (code "44") (name "Net-(R32-Pad2)") (class "Default")
      (node (ref "R32") (pin "2") (pinfunction "2_2") (pintype "passive"))
      (node (ref "R36") (pin "1") (pinfunction "1_1") (pintype "passive"))
    )
    (net (code "45") (name "Net-(R122-Pad2)") (class "Default")
      (node (ref "R122") (pin "2") (pinfunction "2_2") (pintype "passive"))
      (node (ref "R126") (pin "1") (pinfunction "1_1") (pintype "passive"))
    )
    (net (code "46") (name "Net-(R123-Pad2)") (class "Default")
      (node (ref "R123") (pin "2") (pinfunction "2_2") (pintype "passive"))
      (node (ref "R127") (pin "1") (pinfunction "1_1") (pintype "passive"))
    )
    (net (code "47") (name "Net-(R124-Pad2)") (class "Default")
      (node (ref "R124") (pin "2") (pinfunction "2_2") (pintype "passive"))
      (node (ref "R128") (pin "1") (pinfunction "1_1") (pintype "passive"))
    )
    (net (code "48") (name "Net-(R126-Pad2)") (class "Default")
      (node (ref "R126") (pin "2") (pinfunction "2_2") (pintype "passive"))
      (node (ref "R130") (pin "1") (pinfunction "1_1") (pintype "passive"))
    )
    (net (code "49") (name "Net-(R127-Pad2)") (class "Default")
      (node (ref "R127") (pin "2") (pinfunction "2_2") (pintype "passive"))
      (node (ref "R131") (pin "1") (pinfunction "1_1") (pintype "passive"))
    )
    (net (code "50") (name "Net-(R128-Pad2)") (class "Default")
      (node (ref "R128") (pin "2") (pinfunction "2_2") (pintype "passive"))
      (node (ref "R132") (pin "1") (pinfunction "1_1") (pintype "passive"))
    )
    (net (code "51") (name "Net-(R130-Pad2)") (class "Default")
      (node (ref "R130") (pin "2") (pinfunction "2_2") (pintype "passive"))
      (node (ref "R134") (pin "1") (pinfunction "1_1") (pintype "passive"))
    )
    (net (code "52") (name "Net-(R131-Pad2)") (class "Default")
      (node (ref "R131") (pin "2") (pinfunction "2_2") (pintype "passive"))
      (node (ref "R135") (pin "1") (pinfunction "1_1") (pintype "passive"))
    )
    (net (code "53") (name "Net-(R132-Pad2)") (class "Default")
      (node (ref "R132") (pin "2") (pinfunction "2_2") (pintype "passive"))
      (node (ref "R136") (pin "1") (pinfunction "1_1") (pintype "passive"))
    )
    (net (code "54") (name "Net-(R134-Pad2)") (class "Default")
      (node (ref "R134") (pin "2") (pinfunction "2_2") (pintype "passive"))
      (node (ref "R138") (pin "1") (pinfunction "1_1") (pintype "passive"))
    )
    (net (code "55") (name "Net-(R135-Pad2)") (class "Default")
      (node (ref "R135") (pin "2") (pinfunction "2_2") (pintype "passive"))
      (node (ref "R139") (pin "1") (pinfunction "1_1") (pintype "passive"))
    )
    (net (code "56") (name "Net-(R136-Pad2)") (class "Default")
      (node (ref "R136") (pin "2") (pinfunction "2_2") (pintype "passive"))
      (node (ref "R140") (pin "1") (pinfunction "1_1") (pintype "passive"))
    )
    (net (code "57") (name "Net-(R138-Pad2)") (class "Default")
      (node (ref "R138") (pin "2") (pinfunction "2_2") (pintype "passive"))
      (node (ref "R142") (pin "1") (pinfunction "1_1") (pintype "passive"))
    )
    (net (code "58") (name "Net-(R139-Pad2)") (class "Default")
      (node (ref "R139") (pin "2") (pinfunction "2_2") (pintype "passive"))
      (node (ref "R143") (pin "1") (pinfunction "1_1") (pintype "passive"))
    )
    (net (code "59") (name "Net-(R140-Pad2)") (class "Default")
      (node (ref "R140") (pin "2") (pinfunction "2_2") (pintype "passive"))
      (node (ref "R144") (pin "1") (pinfunction "1_1") (pintype "passive"))
    )
    (net (code "60") (name "Net-(U1-+IN)") (class "Default")
      (node (ref "R37") (pin "2") (pinfunction "2_2") (pintype "passive"))
      (node (ref "U1") (pin "3") (pinfunction "+IN_3") (pintype "input"))
    )
    (net (code "61") (name "Net-(U1--IN)") (class "Default")
      (node (ref "R153") (pin "2") (pinfunction "2_2") (pintype "passive"))
      (node (ref "U1") (pin "4") (pinfunction "-IN_4") (pintype "input"))
    )
    (net (code "62") (name "Net-(U1-OUT)") (class "Default")
      (node (ref "C60") (pin "2") (pinfunction "2_2") (pintype "passive"))
      (node (ref "R152") (pin "2") (pinfunction "2_2") (pintype "passive"))
      (node (ref "R54") (pin "1") (pinfunction "1_1") (pintype "passive"))
      (node (ref "U1") (pin "1") (pinfunction "OUT_1") (pintype "output"))
    )
    (net (code "63") (name "Net-(U2-+IN)") (class "Default")
      (node (ref "R39") (pin "2") (pinfunction "2_2") (pintype "passive"))
      (node (ref "U2") (pin "3") (pinfunction "+IN_3") (pintype "input"))
    )
    (net (code "64") (name "Net-(U2--IN)") (class "Default")
      (node (ref "R151") (pin "2") (pinfunction "2_2") (pintype "passive"))
      (node (ref "U2") (pin "4") (pinfunction "-IN_4") (pintype "input"))
    )
    (net (code "65") (name "Net-(U2-OUT)") (class "Default")
      (node (ref "C59") (pin "2") (pinfunction "2_2") (pintype "passive"))
      (node (ref "R150") (pin "1") (pinfunction "1_1") (pintype "passive"))
      (node (ref "R53") (pin "1") (pinfunction "1_1") (pintype "passive"))
      (node (ref "U2") (pin "1") (pinfunction "OUT_1") (pintype "output"))
    )
    (net (code "66") (name "Net-(U3-+IN)") (class "Default")
      (node (ref "R41") (pin "2") (pinfunction "2_2") (pintype "passive"))
      (node (ref "U3") (pin "3") (pinfunction "+IN_3") (pintype "input"))
    )
    (net (code "67") (name "Net-(U3--IN)") (class "Default")
      (node (ref "R149") (pin "2") (pinfunction "2_2") (pintype "passive"))
      (node (ref "U3") (pin "4") (pinfunction "-IN_4") (pintype "input"))
    )
    (net (code "68") (name "Net-(U3-OUT)") (class "Default")
      (node (ref "C58") (pin "2") (pinfunction "2_2") (pintype "passive"))
      (node (ref "R148") (pin "1") (pinfunction "1_1") (pintype "passive"))
      (node (ref "R46") (pin "1") (pinfunction "1_1") (pintype "passive"))
      (node (ref "U3") (pin "1") (pinfunction "OUT_1") (pintype "output"))
    )
    (net (code "69") (name "Net-(U4-+IN)") (class "Default")
      (node (ref "R43") (pin "2") (pinfunction "2_2") (pintype "passive"))
      (node (ref "U4") (pin "3") (pinfunction "+IN_3") (pintype "input"))
    )
    (net (code "70") (name "Net-(U4--IN)") (class "Default")
      (node (ref "R147") (pin "2") (pinfunction "2_2") (pintype "passive"))
      (node (ref "U4") (pin "4") (pinfunction "-IN_4") (pintype "input"))
    )
    (net (code "71") (name "Net-(U4-OUT)") (class "Default")
      (node (ref "C57") (pin "2") (pinfunction "2_2") (pintype "passive"))
      (node (ref "R146") (pin "1") (pinfunction "1_1") (pintype "passive"))
      (node (ref "R45") (pin "1") (pinfunction "1_1") (pintype "passive"))
      (node (ref "U4") (pin "1") (pinfunction "OUT_1") (pintype "output"))
    )
    (net (code "72") (name "VDC_MEAS") (class "Default")
      (node (ref "C72") (pin "1") (pinfunction "1_1") (pintype "passive"))
      (node (ref "R54") (pin "2") (pinfunction "2_2") (pintype "passive"))
    )
    (net (code "73") (name "VU_MEAS") (class "Default")
      (node (ref "C65") (pin "1") (pinfunction "1_1") (pintype "passive"))
      (node (ref "R45") (pin "2") (pinfunction "2_2") (pintype "passive"))
    )
    (net (code "74") (name "VV_MEAS") (class "Default")
      (node (ref "C66") (pin "1") (pinfunction "1_1") (pintype "passive"))
      (node (ref "R46") (pin "2") (pinfunction "2_2") (pintype "passive"))
    )
    (net (code "75") (name "VW_MEAS") (class "Default")
      (node (ref "C68") (pin "1") (pinfunction "1_1") (pintype "passive"))
      (node (ref "R53") (pin "2") (pinfunction "2_2") (pintype "passive"))
    )
  )
)
